# Excercise_001_Completed.net
KiCad netlist of a schematic drawn in EAGLE
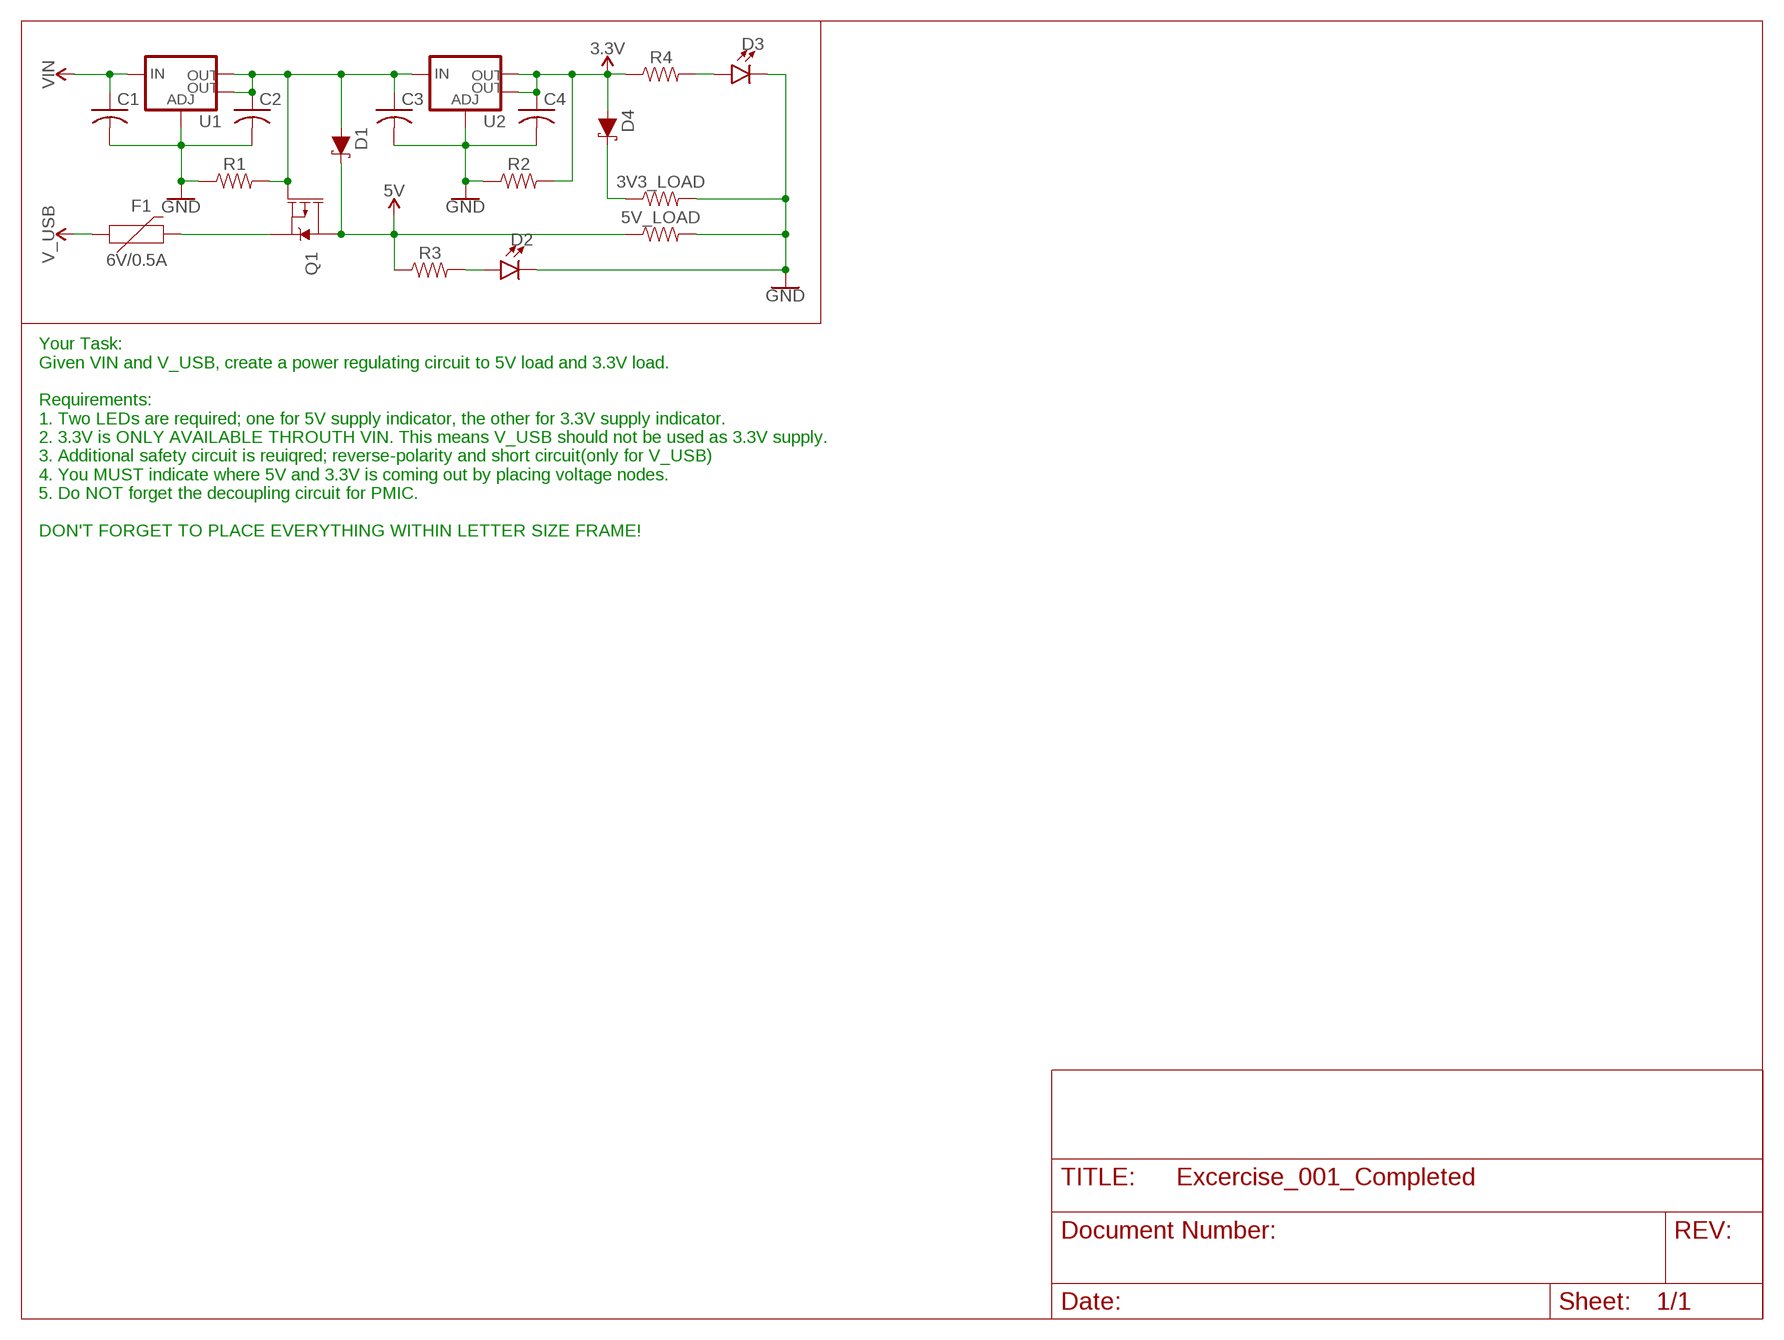
[diagram p0: schematic, sheet 1]

(export (version "E")
  (design (tool "Eeschema 10.0.6"))
  (components
    (comp (ref "3V3_LOAD")
      (value "RESISTOR0805")
      (footprint "eagle-import:0805")
      (libsource (lib "eagle-import") (part "RESISTOR0805"))
    )
    (comp (ref "5V_LOAD")
      (value "RESISTOR0805")
      (footprint "eagle-import:0805")
      (libsource (lib "eagle-import") (part "RESISTOR0805"))
    )
    (comp (ref "C1")
      (value "C-USC0805")
      (footprint "eagle-import:C0805")
      (libsource (lib "eagle-import") (part "C-USC0805"))
    )
    (comp (ref "C2")
      (value "C-USC0805")
      (footprint "eagle-import:C0805")
      (libsource (lib "eagle-import") (part "C-USC0805"))
    )
    (comp (ref "C3")
      (value "C-USC0805")
      (footprint "eagle-import:C0805")
      (libsource (lib "eagle-import") (part "C-USC0805"))
    )
    (comp (ref "C4")
      (value "C-USC0805")
      (footprint "eagle-import:C0805")
      (libsource (lib "eagle-import") (part "C-USC0805"))
    )
    (comp (ref "D1")
      (value "DIODE-SCHOTTKY-B340A")
      (footprint "eagle-import:SMA-DIODE")
      (libsource (lib "eagle-import") (part "DIODE-SCHOTTKY-B340A"))
    )
    (comp (ref "D2")
      (value "LED5MM")
      (footprint "eagle-import:LED_5MM")
      (libsource (lib "eagle-import") (part "LED5MM"))
    )
    (comp (ref "D3")
      (value "LED5MM")
      (footprint "eagle-import:LED_5MM")
      (libsource (lib "eagle-import") (part "LED5MM"))
    )
    (comp (ref "D4")
      (value "DIODE-SCHOTTKY-B340A")
      (footprint "eagle-import:SMA-DIODE")
      (libsource (lib "eagle-import") (part "DIODE-SCHOTTKY-B340A"))
    )
    (comp (ref "F1")
      (value "6V/0.5A")
      (footprint "eagle-import:1206")
      (libsource (lib "eagle-import") (part "PPTC_HALF-AMP"))
    )
    (comp (ref "Q1")
      (value "MOSFET_PCH-NDP6020P")
      (footprint "eagle-import:TO220V")
      (libsource (lib "eagle-import") (part "MOSFET_PCH-NDP6020P"))
    )
    (comp (ref "R1")
      (value "RESISTOR0805")
      (footprint "eagle-import:0805")
      (libsource (lib "eagle-import") (part "RESISTOR0805"))
    )
    (comp (ref "R2")
      (value "RESISTOR0805")
      (footprint "eagle-import:0805")
      (libsource (lib "eagle-import") (part "RESISTOR0805"))
    )
    (comp (ref "R3")
      (value "RESISTOR0805")
      (footprint "eagle-import:0805")
      (libsource (lib "eagle-import") (part "RESISTOR0805"))
    )
    (comp (ref "R4")
      (value "RESISTOR0805")
      (footprint "eagle-import:0805")
      (libsource (lib "eagle-import") (part "RESISTOR0805"))
    )
    (comp (ref "U1")
      (value "V_REG_LM1117SOT223")
      (footprint "eagle-import:SOT223")
      (libsource (lib "eagle-import") (part "V_REG_LM1117SOT223"))
    )
    (comp (ref "U2")
      (value "V_REG_LM1117SOT223")
      (footprint "eagle-import:SOT223")
      (libsource (lib "eagle-import") (part "V_REG_LM1117SOT223"))
    )
  )
  (nets
    (net (code "1") (name "3.3V") (class "Default")
      (node (ref "C4") (pin "1") (pinfunction "1_1") (pintype "passive"))
      (node (ref "D4") (pin "A") (pinfunction "A_A") (pintype "passive"))
      (node (ref "R2") (pin "2") (pinfunction "2_2") (pintype "passive"))
      (node (ref "R4") (pin "1") (pinfunction "1_1") (pintype "passive"))
      (node (ref "U2") (pin "2") (pinfunction "OUT_2") (pintype "output"))
      (node (ref "U2") (pin "4") (pinfunction "OUT_4") (pintype "output"))
    )
    (net (code "2") (name "5V") (class "Default")
      (node (ref "5V_LOAD") (pin "1") (pinfunction "1_1") (pintype "passive"))
      (node (ref "D1") (pin "C") (pinfunction "C_C") (pintype "passive"))
      (node (ref "Q1") (pin "2") (pinfunction "D_2") (pintype "bidirectional"))
      (node (ref "R3") (pin "1") (pinfunction "1_1") (pintype "passive"))
    )
    (net (code "3") (name "GND") (class "Default")
      (node (ref "3V3_LOAD") (pin "2") (pinfunction "2_2") (pintype "passive"))
      (node (ref "5V_LOAD") (pin "2") (pinfunction "2_2") (pintype "passive"))
      (node (ref "C1") (pin "2") (pinfunction "2_2") (pintype "passive"))
      (node (ref "C2") (pin "2") (pinfunction "2_2") (pintype "passive"))
      (node (ref "C3") (pin "2") (pinfunction "2_2") (pintype "passive"))
      (node (ref "C4") (pin "2") (pinfunction "2_2") (pintype "passive"))
      (node (ref "D2") (pin "K") (pinfunction "C_K") (pintype "passive"))
      (node (ref "D3") (pin "K") (pinfunction "C_K") (pintype "passive"))
      (node (ref "R1") (pin "1") (pinfunction "1_1") (pintype "passive"))
      (node (ref "R2") (pin "1") (pinfunction "1_1") (pintype "passive"))
      (node (ref "U1") (pin "1") (pinfunction "ADJ_1") (pintype "input"))
      (node (ref "U2") (pin "1") (pinfunction "ADJ_1") (pintype "input"))
    )
    (net (code "4") (name "Net-(3V3_LOAD-Pad1)") (class "Default")
      (node (ref "3V3_LOAD") (pin "1") (pinfunction "1_1") (pintype "passive"))
      (node (ref "D4") (pin "C") (pinfunction "C_C") (pintype "passive"))
    )
    (net (code "5") (name "Net-(D2-PadA)") (class "Default")
      (node (ref "D2") (pin "A") (pinfunction "A_A") (pintype "passive"))
      (node (ref "R3") (pin "2") (pinfunction "2_2") (pintype "passive"))
    )
    (net (code "6") (name "Net-(D3-PadA)") (class "Default")
      (node (ref "D3") (pin "A") (pinfunction "A_A") (pintype "passive"))
      (node (ref "R4") (pin "2") (pinfunction "2_2") (pintype "passive"))
    )
    (net (code "7") (name "Net-(Q1-G)") (class "Default")
      (node (ref "C2") (pin "1") (pinfunction "1_1") (pintype "passive"))
      (node (ref "C3") (pin "1") (pinfunction "1_1") (pintype "passive"))
      (node (ref "D1") (pin "A") (pinfunction "A_A") (pintype "passive"))
      (node (ref "Q1") (pin "1") (pinfunction "G_1") (pintype "bidirectional"))
      (node (ref "R1") (pin "2") (pinfunction "2_2") (pintype "passive"))
      (node (ref "U1") (pin "2") (pinfunction "OUT_2") (pintype "output"))
      (node (ref "U1") (pin "4") (pinfunction "OUT_4") (pintype "output"))
      (node (ref "U2") (pin "3") (pinfunction "IN_3") (pintype "input"))
    )
    (net (code "8") (name "Net-(Q1-S)") (class "Default")
      (node (ref "F1") (pin "2") (pinfunction "2_2") (pintype "bidirectional"))
      (node (ref "Q1") (pin "3") (pinfunction "S_3") (pintype "bidirectional"))
    )
    (net (code "9") (name "VIN") (class "Default")
      (node (ref "C1") (pin "1") (pinfunction "1_1") (pintype "passive"))
      (node (ref "U1") (pin "3") (pinfunction "IN_3") (pintype "input"))
    )
    (net (code "10") (name "V_USB") (class "Default")
      (node (ref "F1") (pin "1") (pinfunction "1_1") (pintype "bidirectional"))
    )
  )
)
